# 07-DPLL-1.net
KiCad netlist of a schematic drawn in Altium Designer
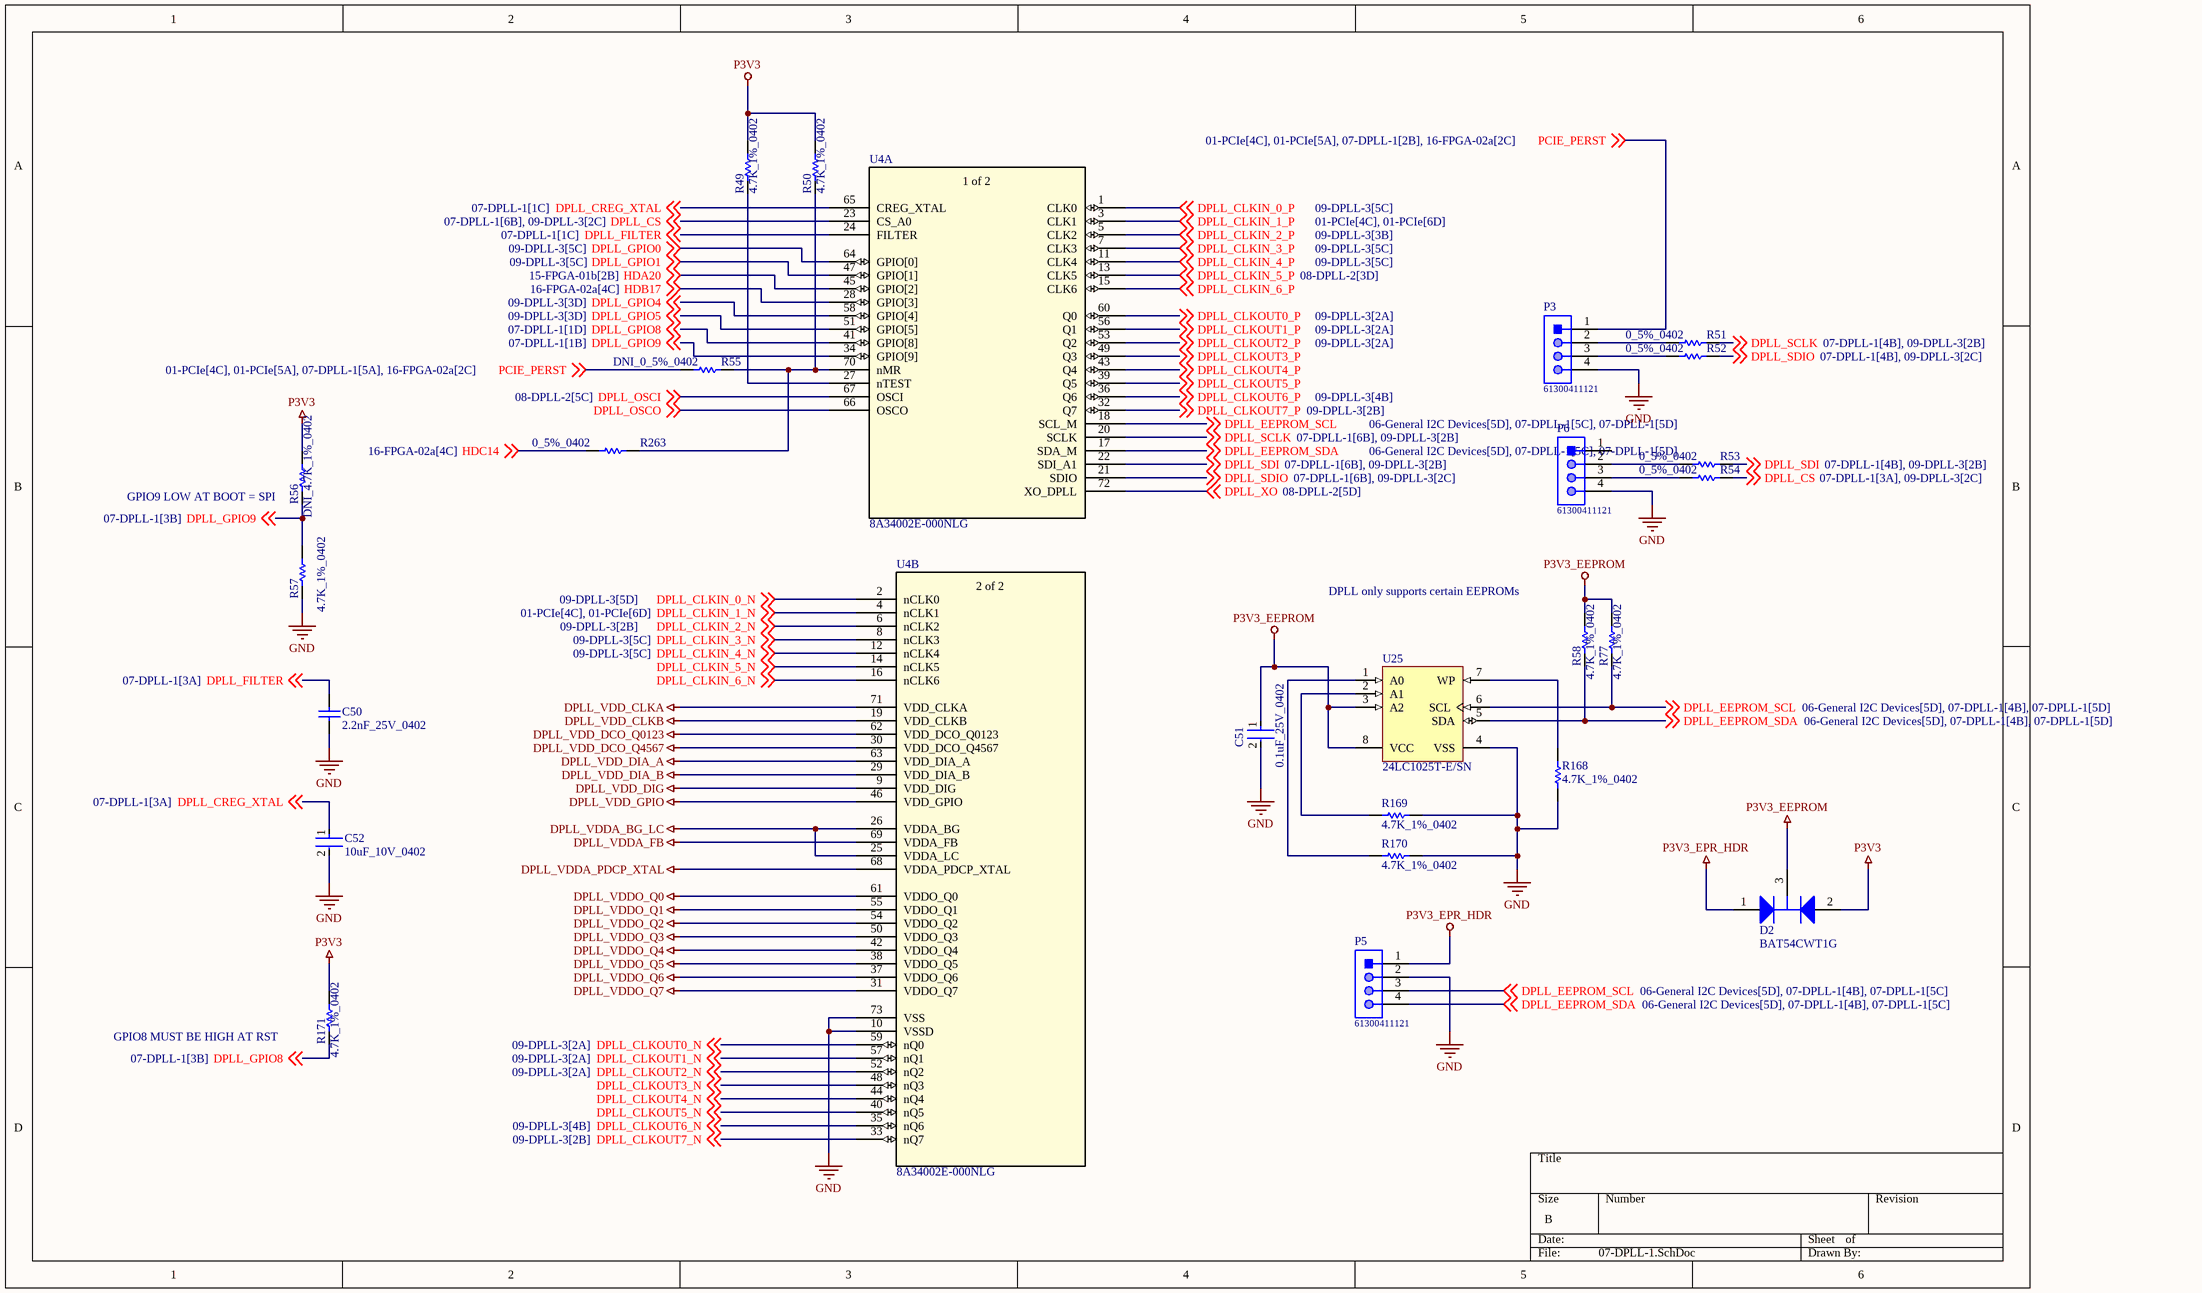
[diagram p0: 07-DPLL-1.SchDoc]

(export (version "E")
  (design (tool "Eeschema 10.0.6"))
  (components
    (comp (ref "C50")
      (value "2.2nF_25V_0402")
      (footprint "CAPC1005X56X25LL10T15")
      (fields
        (field (name "MANUFACTURER") "AVX Interconnect / Elco")
        (field (name "PART NUMBER") "04025C222JAT2A")
      )
      (libsource (lib "Altium Content Vault") (part "CAP"))
    )
    (comp (ref "C51")
      (value "0.1uF_25V_0402")
      (footprint "FP-0402-L_1_0_1-W_0_5_0_1-IPC_C")
      (description "General Purpose Ceramic Capacitor, 0402, 100nF, 10%, X7R, 15%, 25V")
      (fields (field (name "VOLTAGE") "25V") (field (name "TOLERANCE") "10%"))
      (libsource (lib "Altium Content Vault") (part "b4654b650e69147ec39a6b967a45e02"))
    )
    (comp (ref "C52")
      (value "10uF_10V_0402")
      (footprint "FP-CL05A106MP5NUNC-MFG")
      (description "CAP CER 10UF 10V X5R 0402")
      (fields
        (field (name "OCTOPART") "https://octopart.com/cl05a106mp5nunc-samsung-22457395")
        (field (name "TOLERANCE") "20%")
      )
      (libsource (lib "Altium Content Vault") (part "b4654b650e69147ec39a6b967a45e02"))
    )
    (comp (ref "D2")
      (value "BAT54CWT1G")
      (footprint "ONSC-SOT-323-3-419-04_V")
      (description "Dual Series Cathode Schottky Barrier Diodes, 3-Pin SOT-323, Pb-Free, Tape and Reel")
      (fields (field (name "MANUFACTURER") "On Semiconductor"))
      (libsource (lib "Altium Content Vault") (part "ONSC-D-A1A2K3-3"))
    )
    (comp (ref "P3")
      (value "61300411121")
      (footprint "61300411121")
      (description "THT Vertical Pin Header WR-PHD, Pitch 2.54 mm, Single Row, 4 pins")
      (fields (field (name "MANUFACTURER") "Wurth Elektronik") (field (name "PUBLISHER") "WurthElektronik"))
      (libsource (lib "Altium Content Vault") (part "WE-CN-1P-M-R4"))
    )
    (comp (ref "P5")
      (value "61300411121")
      (footprint "61300411121")
      (description "THT Vertical Pin Header WR-PHD, Pitch 2.54 mm, Single Row, 4 pins")
      (fields (field (name "MANUFACTURER") "Wurth Elektronik") (field (name "PUBLISHER") "WurthElektronik"))
      (libsource (lib "Altium Content Vault") (part "WE-CN-1P-M-R4"))
    )
    (comp (ref "P6")
      (value "61300411121")
      (footprint "61300411121")
      (description "THT Vertical Pin Header WR-PHD, Pitch 2.54 mm, Single Row, 4 pins")
      (fields (field (name "MANUFACTURER") "Wurth Elektronik") (field (name "PUBLISHER") "WurthElektronik"))
      (libsource (lib "Altium Content Vault") (part "WE-CN-1P-M-R4"))
    )
    (comp (ref "R49")
      (value "4.7K_1%_0402")
      (footprint "RESC1005X40X25NL10T10")
      (fields (field (name "MANUFACTURER") "Bourns") (field (name "PART NUMBER") "CR0402-FX-4701GLF"))
      (libsource (lib "Altium Content Vault") (part "RES"))
    )
    (comp (ref "R50")
      (value "4.7K_1%_0402")
      (footprint "RESC1005X40X25NL10T10")
      (fields (field (name "MANUFACTURER") "Bourns") (field (name "PART NUMBER") "CR0402-FX-4701GLF"))
      (libsource (lib "Altium Content Vault") (part "RES"))
    )
    (comp (ref "R51")
      (value "0_5%_0402")
      (footprint "RESC1005X40X25LL10T10")
      (fields (field (name "MANUFACTURER") "KOA Speer") (field (name "PART NUMBER") "RK73Z1ETTP"))
      (libsource (lib "Altium Content Vault") (part "RES"))
    )
    (comp (ref "R52")
      (value "0_5%_0402")
      (footprint "RESC1005X40X25LL10T10")
      (fields (field (name "MANUFACTURER") "KOA Speer") (field (name "PART NUMBER") "RK73Z1ETTP"))
      (libsource (lib "Altium Content Vault") (part "RES"))
    )
    (comp (ref "R53")
      (value "0_5%_0402")
      (footprint "RESC1005X40X25LL10T10")
      (fields (field (name "MANUFACTURER") "KOA Speer") (field (name "PART NUMBER") "RK73Z1ETTP"))
      (libsource (lib "Altium Content Vault") (part "RES"))
    )
    (comp (ref "R54")
      (value "0_5%_0402")
      (footprint "RESC1005X40X25LL10T10")
      (fields (field (name "MANUFACTURER") "KOA Speer") (field (name "PART NUMBER") "RK73Z1ETTP"))
      (libsource (lib "Altium Content Vault") (part "RES"))
    )
    (comp (ref "R55")
      (value "DNI_0_5%_0402")
      (footprint "RESC1005X40X25LL10T10")
      (fields (field (name "MANUFACTURER") "KOA Speer") (field (name "PART NUMBER") "RK73Z1ETTP"))
      (libsource (lib "Altium Content Vault") (part "RES"))
    )
    (comp (ref "R56")
      (value "DNI_4.7K_1%_0402")
      (footprint "RESC1005X40X25NL10T10")
      (fields (field (name "MANUFACTURER") "Bourns") (field (name "PART NUMBER") "CR0402-FX-4701GLF"))
      (libsource (lib "Altium Content Vault") (part "RES"))
    )
    (comp (ref "R57")
      (value "4.7K_1%_0402")
      (footprint "RESC1005X40X25NL10T10")
      (fields (field (name "MANUFACTURER") "Bourns") (field (name "PART NUMBER") "CR0402-FX-4701GLF"))
      (libsource (lib "Altium Content Vault") (part "RES"))
    )
    (comp (ref "R58")
      (value "4.7K_1%_0402")
      (footprint "RESC1005X40X25NL10T10")
      (fields (field (name "MANUFACTURER") "Bourns") (field (name "PART NUMBER") "CR0402-FX-4701GLF"))
      (libsource (lib "Altium Content Vault") (part "RES"))
    )
    (comp (ref "R77")
      (value "4.7K_1%_0402")
      (footprint "RESC1005X40X25NL10T10")
      (fields (field (name "MANUFACTURER") "Bourns") (field (name "PART NUMBER") "CR0402-FX-4701GLF"))
      (libsource (lib "Altium Content Vault") (part "RES"))
    )
    (comp (ref "R168")
      (value "4.7K_1%_0402")
      (footprint "RESC1005X40X25NL10T10")
      (fields (field (name "MANUFACTURER") "Bourns") (field (name "PART NUMBER") "CR0402-FX-4701GLF"))
      (libsource (lib "Altium Content Vault") (part "RES"))
    )
    (comp (ref "R169")
      (value "4.7K_1%_0402")
      (footprint "RESC1005X40X25NL10T10")
      (fields (field (name "MANUFACTURER") "Bourns") (field (name "PART NUMBER") "CR0402-FX-4701GLF"))
      (libsource (lib "Altium Content Vault") (part "RES"))
    )
    (comp (ref "R170")
      (value "4.7K_1%_0402")
      (footprint "RESC1005X40X25NL10T10")
      (fields (field (name "MANUFACTURER") "Bourns") (field (name "PART NUMBER") "CR0402-FX-4701GLF"))
      (libsource (lib "Altium Content Vault") (part "RES"))
    )
    (comp (ref "R171")
      (value "4.7K_1%_0402")
      (footprint "RESC1005X40X25NL10T10")
      (fields (field (name "MANUFACTURER") "Bourns") (field (name "PART NUMBER") "CR0402-FX-4701GLF"))
      (libsource (lib "Altium Content Vault") (part "RES"))
    )
    (comp (ref "R263")
      (value "0_5%_0402")
      (footprint "RESC1005X40X25LL10T10")
      (fields (field (name "MANUFACTURER") "KOA Speer") (field (name "PART NUMBER") "RK73Z1ETTP"))
      (libsource (lib "Altium Content Vault") (part "RES"))
    )
    (comp (ref "U4")
      (value "8A34002E-000NLG")
      (footprint "QFN_2E-000NLG_REN")
      (description "No Description Available")
      (libsource (lib "8A34002E-000NLG") (part "8A34002E-000NLG"))
    )
    (comp (ref "U25")
      (value "24LC1025T-E/SN")
      (footprint "SOIC-SN8_M")
      (description "1 Mbit, 400kHz, 2.5V, 8-Pin SOIC 150mil, Extended Temperature, Tape and Reel")
      (libsource (lib "Altium Content Vault") (part "MEM-SEEPROM-34AA02-IL8"))
    )
  )
  (nets
    (net (code "1") (name "DPLL_CLKIN_0_N") (class "Default")
      (node (ref "U4") (pin "2") (pinfunction "nCLK0_2") (pintype "passive"))
    )
    (net (code "2") (name "DPLL_CLKIN_0_P") (class "Default")
      (node (ref "U4") (pin "1") (pinfunction "CLK0_1") (pintype "bidirectional"))
    )
    (net (code "3") (name "DPLL_CLKIN_1_N") (class "Default")
      (node (ref "U4") (pin "4") (pinfunction "nCLK1_4") (pintype "passive"))
    )
    (net (code "4") (name "DPLL_CLKIN_1_P") (class "Default")
      (node (ref "U4") (pin "3") (pinfunction "CLK1_3") (pintype "bidirectional"))
    )
    (net (code "5") (name "DPLL_CLKIN_2_N") (class "Default")
      (node (ref "U4") (pin "6") (pinfunction "nCLK2_6") (pintype "passive"))
    )
    (net (code "6") (name "DPLL_CLKIN_2_P") (class "Default")
      (node (ref "U4") (pin "5") (pinfunction "CLK2_5") (pintype "bidirectional"))
    )
    (net (code "7") (name "DPLL_CLKIN_3_N") (class "Default")
      (node (ref "U4") (pin "8") (pinfunction "nCLK3_8") (pintype "passive"))
    )
    (net (code "8") (name "DPLL_CLKIN_3_P") (class "Default")
      (node (ref "U4") (pin "7") (pinfunction "CLK3_7") (pintype "bidirectional"))
    )
    (net (code "9") (name "DPLL_CLKIN_4_N") (class "Default")
      (node (ref "U4") (pin "12") (pinfunction "nCLK4_12") (pintype "passive"))
    )
    (net (code "10") (name "DPLL_CLKIN_4_P") (class "Default")
      (node (ref "U4") (pin "11") (pinfunction "CLK4_11") (pintype "bidirectional"))
    )
    (net (code "11") (name "DPLL_CLKIN_5_N") (class "Default")
      (node (ref "U4") (pin "14") (pinfunction "nCLK5_14") (pintype "passive"))
    )
    (net (code "12") (name "DPLL_CLKIN_5_P") (class "Default")
      (node (ref "U4") (pin "13") (pinfunction "CLK5_13") (pintype "bidirectional"))
    )
    (net (code "13") (name "DPLL_CLKIN_6_N") (class "Default")
      (node (ref "U4") (pin "16") (pinfunction "nCLK6_16") (pintype "passive"))
    )
    (net (code "14") (name "DPLL_CLKIN_6_P") (class "Default")
      (node (ref "U4") (pin "15") (pinfunction "CLK6_15") (pintype "bidirectional"))
    )
    (net (code "15") (name "DPLL_CLKOUT0_N") (class "Default")
      (node (ref "U4") (pin "59") (pinfunction "nQ0_59") (pintype "bidirectional"))
    )
    (net (code "16") (name "DPLL_CLKOUT0_P") (class "Default")
      (node (ref "U4") (pin "60") (pinfunction "Q0_60") (pintype "bidirectional"))
    )
    (net (code "17") (name "DPLL_CLKOUT1_N") (class "Default")
      (node (ref "U4") (pin "57") (pinfunction "nQ1_57") (pintype "bidirectional"))
    )
    (net (code "18") (name "DPLL_CLKOUT1_P") (class "Default")
      (node (ref "U4") (pin "56") (pinfunction "Q1_56") (pintype "bidirectional"))
    )
    (net (code "19") (name "DPLL_CLKOUT2_N") (class "Default")
      (node (ref "U4") (pin "52") (pinfunction "nQ2_52") (pintype "bidirectional"))
    )
    (net (code "20") (name "DPLL_CLKOUT2_P") (class "Default")
      (node (ref "U4") (pin "53") (pinfunction "Q2_53") (pintype "bidirectional"))
    )
    (net (code "21") (name "DPLL_CLKOUT3_N") (class "Default")
      (node (ref "U4") (pin "48") (pinfunction "nQ3_48") (pintype "bidirectional"))
    )
    (net (code "22") (name "DPLL_CLKOUT3_P") (class "Default")
      (node (ref "U4") (pin "49") (pinfunction "Q3_49") (pintype "bidirectional"))
    )
    (net (code "23") (name "DPLL_CLKOUT4_N") (class "Default")
      (node (ref "U4") (pin "44") (pinfunction "nQ4_44") (pintype "bidirectional"))
    )
    (net (code "24") (name "DPLL_CLKOUT4_P") (class "Default")
      (node (ref "U4") (pin "43") (pinfunction "Q4_43") (pintype "bidirectional"))
    )
    (net (code "25") (name "DPLL_CLKOUT5_N") (class "Default")
      (node (ref "U4") (pin "40") (pinfunction "nQ5_40") (pintype "bidirectional"))
    )
    (net (code "26") (name "DPLL_CLKOUT5_P") (class "Default")
      (node (ref "U4") (pin "39") (pinfunction "Q5_39") (pintype "bidirectional"))
    )
    (net (code "27") (name "DPLL_CLKOUT6_N") (class "Default")
      (node (ref "U4") (pin "35") (pinfunction "nQ6_35") (pintype "bidirectional"))
    )
    (net (code "28") (name "DPLL_CLKOUT6_P") (class "Default")
      (node (ref "U4") (pin "36") (pinfunction "Q6_36") (pintype "bidirectional"))
    )
    (net (code "29") (name "DPLL_CLKOUT7_N") (class "Default")
      (node (ref "U4") (pin "33") (pinfunction "nQ7_33") (pintype "bidirectional"))
    )
    (net (code "30") (name "DPLL_CLKOUT7_P") (class "Default")
      (node (ref "U4") (pin "32") (pinfunction "Q7_32") (pintype "bidirectional"))
    )
    (net (code "31") (name "DPLL_CREG_XTAL") (class "Default")
      (node (ref "C52") (pin "1") (pinfunction "1_1") (pintype "passive"))
      (node (ref "U4") (pin "65") (pinfunction "CREG_XTAL_65") (pintype "passive"))
    )
    (net (code "32") (name "DPLL_CS") (class "Default")
      (node (ref "R54") (pin "2") (pinfunction "2_2") (pintype "passive"))
      (node (ref "U4") (pin "23") (pinfunction "CS_A0_23") (pintype "passive"))
    )
    (net (code "33") (name "DPLL_EEPROM_SCL") (class "Default")
      (node (ref "P5") (pin "3") (pinfunction "3_3") (pintype "passive"))
      (node (ref "R77") (pin "2") (pinfunction "2_2") (pintype "passive"))
      (node (ref "U25") (pin "6") (pinfunction "SCL_6") (pintype "input"))
      (node (ref "U4") (pin "18") (pinfunction "SCL_M_18") (pintype "passive"))
    )
    (net (code "34") (name "DPLL_EEPROM_SDA") (class "Default")
      (node (ref "P5") (pin "4") (pinfunction "4_4") (pintype "passive"))
      (node (ref "R58") (pin "2") (pinfunction "2_2") (pintype "passive"))
      (node (ref "U25") (pin "5") (pinfunction "SDA_5") (pintype "bidirectional"))
      (node (ref "U4") (pin "17") (pinfunction "SDA_M_17") (pintype "passive"))
    )
    (net (code "35") (name "DPLL_FILTER") (class "Default")
      (node (ref "C50") (pin "2") (pinfunction "2_2") (pintype "passive"))
      (node (ref "U4") (pin "24") (pinfunction "FILTER_24") (pintype "passive"))
    )
    (net (code "36") (name "DPLL_GPIO0") (class "Default")
      (node (ref "U4") (pin "64") (pinfunction "GPIO[0]_64") (pintype "bidirectional"))
    )
    (net (code "37") (name "DPLL_GPIO1") (class "Default")
      (node (ref "U4") (pin "47") (pinfunction "GPIO[1]_47") (pintype "bidirectional"))
    )
    (net (code "38") (name "DPLL_GPIO4") (class "Default")
      (node (ref "U4") (pin "58") (pinfunction "GPIO[4]_58") (pintype "bidirectional"))
    )
    (net (code "39") (name "DPLL_GPIO5") (class "Default")
      (node (ref "U4") (pin "51") (pinfunction "GPIO[5]_51") (pintype "bidirectional"))
    )
    (net (code "40") (name "DPLL_GPIO8") (class "Default")
      (node (ref "R171") (pin "2") (pinfunction "2_2") (pintype "passive"))
      (node (ref "U4") (pin "41") (pinfunction "GPIO[8]_41") (pintype "bidirectional"))
    )
    (net (code "41") (name "DPLL_GPIO9") (class "Default")
      (node (ref "R56") (pin "2") (pinfunction "2_2") (pintype "passive"))
      (node (ref "R57") (pin "2") (pinfunction "2_2") (pintype "passive"))
      (node (ref "U4") (pin "34") (pinfunction "GPIO[9]_34") (pintype "bidirectional"))
    )
    (net (code "42") (name "DPLL_OSCI") (class "Default")
      (node (ref "U4") (pin "67") (pinfunction "OSCI_67") (pintype "passive"))
    )
    (net (code "43") (name "DPLL_OSCO") (class "Default")
      (node (ref "U4") (pin "66") (pinfunction "OSCO_66") (pintype "passive"))
    )
    (net (code "44") (name "DPLL_SCLK") (class "Default")
      (node (ref "R51") (pin "2") (pinfunction "2_2") (pintype "passive"))
      (node (ref "U4") (pin "20") (pinfunction "SCLK_20") (pintype "passive"))
    )
    (net (code "45") (name "DPLL_SDI") (class "Default")
      (node (ref "R53") (pin "2") (pinfunction "2_2") (pintype "passive"))
      (node (ref "U4") (pin "22") (pinfunction "SDI_A1_22") (pintype "passive"))
    )
    (net (code "46") (name "DPLL_SDIO") (class "Default")
      (node (ref "R52") (pin "2") (pinfunction "2_2") (pintype "passive"))
      (node (ref "U4") (pin "21") (pinfunction "SDIO_21") (pintype "passive"))
    )
    (net (code "47") (name "DPLL_VDDA_BG_LC") (class "Default")
      (node (ref "U4") (pin "25") (pinfunction "VDDA_LC_25") (pintype "power_in"))
      (node (ref "U4") (pin "26") (pinfunction "VDDA_BG_26") (pintype "power_in"))
    )
    (net (code "48") (name "DPLL_VDDA_FB") (class "Default")
      (node (ref "U4") (pin "69") (pinfunction "VDDA_FB_69") (pintype "power_in"))
    )
    (net (code "49") (name "DPLL_VDDA_PDCP_XTAL") (class "Default")
      (node (ref "U4") (pin "68") (pinfunction "VDDA_PDCP_XTAL_68") (pintype "power_in"))
    )
    (net (code "50") (name "DPLL_VDDO_Q0") (class "Default")
      (node (ref "U4") (pin "61") (pinfunction "VDDO_Q0_61") (pintype "power_in"))
    )
    (net (code "51") (name "DPLL_VDDO_Q1") (class "Default")
      (node (ref "U4") (pin "55") (pinfunction "VDDO_Q1_55") (pintype "power_in"))
    )
    (net (code "52") (name "DPLL_VDDO_Q2") (class "Default")
      (node (ref "U4") (pin "54") (pinfunction "VDDO_Q2_54") (pintype "power_in"))
    )
    (net (code "53") (name "DPLL_VDDO_Q3") (class "Default")
      (node (ref "U4") (pin "50") (pinfunction "VDDO_Q3_50") (pintype "power_in"))
    )
    (net (code "54") (name "DPLL_VDDO_Q4") (class "Default")
      (node (ref "U4") (pin "42") (pinfunction "VDDO_Q4_42") (pintype "power_in"))
    )
    (net (code "55") (name "DPLL_VDDO_Q5") (class "Default")
      (node (ref "U4") (pin "38") (pinfunction "VDDO_Q5_38") (pintype "power_in"))
    )
    (net (code "56") (name "DPLL_VDDO_Q6") (class "Default")
      (node (ref "U4") (pin "37") (pinfunction "VDDO_Q6_37") (pintype "power_in"))
    )
    (net (code "57") (name "DPLL_VDDO_Q7") (class "Default")
      (node (ref "U4") (pin "31") (pinfunction "VDDO_Q7_31") (pintype "power_in"))
    )
    (net (code "58") (name "DPLL_VDD_CLKA") (class "Default")
      (node (ref "U4") (pin "71") (pinfunction "VDD_CLKA_71") (pintype "power_in"))
    )
    (net (code "59") (name "DPLL_VDD_CLKB") (class "Default")
      (node (ref "U4") (pin "19") (pinfunction "VDD_CLKB_19") (pintype "power_in"))
    )
    (net (code "60") (name "DPLL_VDD_DCO_Q0123") (class "Default")
      (node (ref "U4") (pin "62") (pinfunction "VDD_DCO_Q0123_62") (pintype "power_in"))
    )
    (net (code "61") (name "DPLL_VDD_DCO_Q4567") (class "Default")
      (node (ref "U4") (pin "30") (pinfunction "VDD_DCO_Q4567_30") (pintype "power_in"))
    )
    (net (code "62") (name "DPLL_VDD_DIA_A") (class "Default")
      (node (ref "U4") (pin "63") (pinfunction "VDD_DIA_A_63") (pintype "power_in"))
    )
    (net (code "63") (name "DPLL_VDD_DIA_B") (class "Default")
      (node (ref "U4") (pin "29") (pinfunction "VDD_DIA_B_29") (pintype "power_in"))
    )
    (net (code "64") (name "DPLL_VDD_DIG") (class "Default")
      (node (ref "U4") (pin "9") (pinfunction "VDD_DIG_9") (pintype "power_in"))
    )
    (net (code "65") (name "DPLL_VDD_GPIO") (class "Default")
      (node (ref "U4") (pin "46") (pinfunction "VDD_GPIO_46") (pintype "power_in"))
    )
    (net (code "66") (name "DPLL_XO") (class "Default")
      (node (ref "U4") (pin "72") (pinfunction "XO_DPLL_72") (pintype "passive"))
    )
    (net (code "67") (name "GND") (class "Default")
      (node (ref "C50") (pin "1") (pinfunction "1_1") (pintype "passive"))
      (node (ref "C51") (pin "2") (pinfunction "2_2") (pintype "passive"))
      (node (ref "C52") (pin "2") (pinfunction "2_2") (pintype "passive"))
      (node (ref "P3") (pin "4") (pinfunction "4_4") (pintype "passive"))
      (node (ref "P5") (pin "2") (pinfunction "2_2") (pintype "passive"))
      (node (ref "P6") (pin "4") (pinfunction "4_4") (pintype "passive"))
      (node (ref "R168") (pin "2") (pinfunction "2_2") (pintype "passive"))
      (node (ref "R169") (pin "1") (pinfunction "1_1") (pintype "passive"))
      (node (ref "R170") (pin "2") (pinfunction "2_2") (pintype "passive"))
      (node (ref "R57") (pin "1") (pinfunction "1_1") (pintype "passive"))
      (node (ref "U25") (pin "4") (pinfunction "VSS_4") (pintype "power_in"))
      (node (ref "U4") (pin "10") (pinfunction "VSSD_10") (pintype "power_in"))
      (node (ref "U4") (pin "73") (pinfunction "VSS_73") (pintype "power_in"))
    )
    (net (code "68") (name "HDA20") (class "Default")
      (node (ref "U4") (pin "45") (pinfunction "GPIO[2]_45") (pintype "bidirectional"))
    )
    (net (code "69") (name "HDB17") (class "Default")
      (node (ref "U4") (pin "28") (pinfunction "GPIO[3]_28") (pintype "bidirectional"))
    )
    (net (code "70") (name "HDC14") (class "Default")
      (node (ref "R263") (pin "1") (pinfunction "1_1") (pintype "passive"))
    )
    (net (code "71") (name "Net-(P3-Pad2)") (class "Default")
      (node (ref "P3") (pin "2") (pinfunction "2_2") (pintype "passive"))
      (node (ref "R51") (pin "1") (pinfunction "1_1") (pintype "passive"))
    )
    (net (code "72") (name "Net-(P3-Pad3)") (class "Default")
      (node (ref "P3") (pin "3") (pinfunction "3_3") (pintype "passive"))
      (node (ref "R52") (pin "1") (pinfunction "1_1") (pintype "passive"))
    )
    (net (code "73") (name "Net-(P6-Pad2)") (class "Default")
      (node (ref "P6") (pin "2") (pinfunction "2_2") (pintype "passive"))
      (node (ref "R53") (pin "1") (pinfunction "1_1") (pintype "passive"))
    )
    (net (code "74") (name "Net-(P6-Pad3)") (class "Default")
      (node (ref "P6") (pin "3") (pinfunction "3_3") (pintype "passive"))
      (node (ref "R54") (pin "1") (pinfunction "1_1") (pintype "passive"))
    )
    (net (code "75") (name "Net-(U4A-nMR)") (class "Default")
      (node (ref "R263") (pin "2") (pinfunction "2_2") (pintype "passive"))
      (node (ref "R50") (pin "1") (pinfunction "1_1") (pintype "passive"))
      (node (ref "R55") (pin "2") (pinfunction "2_2") (pintype "passive"))
      (node (ref "U4") (pin "70") (pinfunction "nMR_70") (pintype "passive"))
    )
    (net (code "76") (name "Net-(U4A-nTEST)") (class "Default")
      (node (ref "R49") (pin "1") (pinfunction "1_1") (pintype "passive"))
      (node (ref "U4") (pin "27") (pinfunction "nTEST_27") (pintype "passive"))
    )
    (net (code "77") (name "Net-(U25-A0)") (class "Default")
      (node (ref "R170") (pin "1") (pinfunction "1_1") (pintype "passive"))
      (node (ref "U25") (pin "1") (pinfunction "A0_1") (pintype "input"))
    )
    (net (code "78") (name "Net-(U25-A1)") (class "Default")
      (node (ref "R169") (pin "2") (pinfunction "2_2") (pintype "passive"))
      (node (ref "U25") (pin "2") (pinfunction "A1_2") (pintype "input"))
    )
    (net (code "79") (name "Net-(U25-WP)") (class "Default")
      (node (ref "R168") (pin "1") (pinfunction "1_1") (pintype "passive"))
      (node (ref "U25") (pin "7") (pinfunction "WP_7") (pintype "input"))
    )
    (net (code "80") (name "P3V3") (class "Default")
      (node (ref "D2") (pin "2") (pinfunction "A2_2") (pintype "passive"))
      (node (ref "R171") (pin "1") (pinfunction "1_1") (pintype "passive"))
      (node (ref "R49") (pin "2") (pinfunction "2_2") (pintype "passive"))
      (node (ref "R50") (pin "2") (pinfunction "2_2") (pintype "passive"))
      (node (ref "R56") (pin "1") (pinfunction "1_1") (pintype "passive"))
    )
    (net (code "81") (name "P3V3_EEPROM") (class "Default")
      (node (ref "C51") (pin "1") (pinfunction "1_1") (pintype "passive"))
      (node (ref "D2") (pin "3") (pinfunction "K_3") (pintype "passive"))
      (node (ref "R58") (pin "1") (pinfunction "1_1") (pintype "passive"))
      (node (ref "R77") (pin "1") (pinfunction "1_1") (pintype "passive"))
      (node (ref "U25") (pin "3") (pinfunction "A2_3") (pintype "input"))
      (node (ref "U25") (pin "8") (pinfunction "VCC_8") (pintype "power_in"))
    )
    (net (code "82") (name "P3V3_EPR_HDR") (class "Default")
      (node (ref "D2") (pin "1") (pinfunction "A1_1") (pintype "passive"))
      (node (ref "P5") (pin "1") (pinfunction "1_1") (pintype "passive"))
    )
    (net (code "83") (name "PCIE_PERST") (class "Default")
      (node (ref "P3") (pin "1") (pinfunction "1_1") (pintype "passive"))
      (node (ref "R55") (pin "1") (pinfunction "1_1") (pintype "passive"))
    )
    (net (code "84") (name "unconnected-(P6-Pad1)") (class "Default")
      (node (ref "P6") (pin "1") (pinfunction "1_1") (pintype "passive"))
    )
  )
)
